# sac_4klep.net
KiCad netlist of a schematic drawn in EAGLE
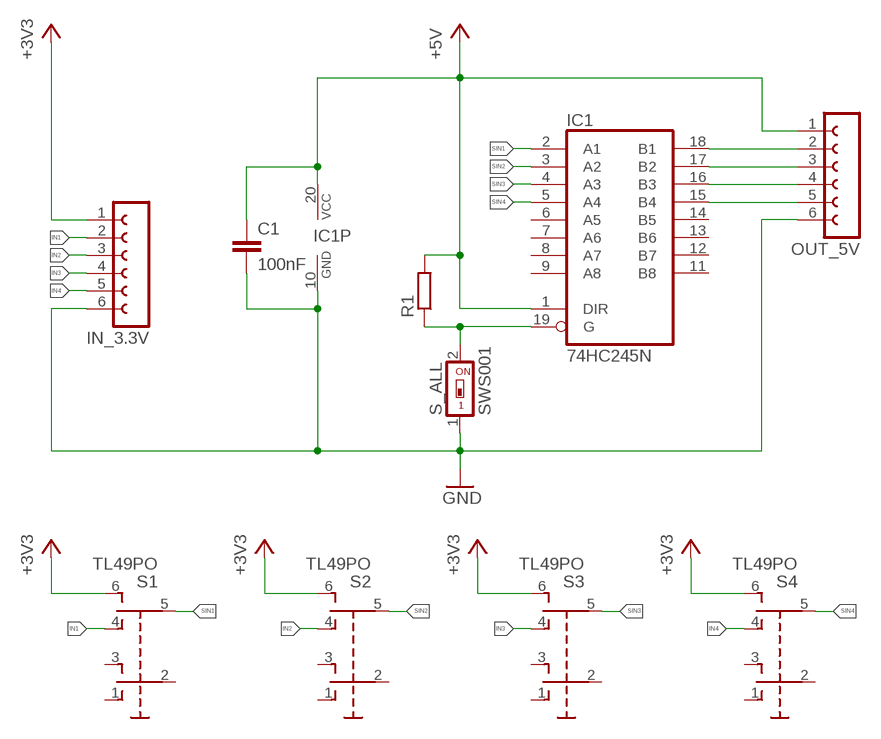
[diagram p0: schematic, sheet 1]

(export (version "E")
  (design (tool "Eeschema 10.0.6"))
  (components
    (comp (ref "C1")
      (value "100nF")
      (footprint "eagle-import:C025-040X050")
      (libsource (lib "eagle-import") (part "C-EU025-040X050"))
    )
    (comp (ref "IC1")
      (value "74HC245N")
      (footprint "eagle-import:DIL20")
      (libsource (lib "eagle-import") (part "74245NHC"))
    )
    (comp (ref "IN_3.3V")
      (value "FE06-1")
      (footprint "eagle-import:FE06")
      (libsource (lib "eagle-import") (part "FE06-1"))
    )
    (comp (ref "OUT_5V")
      (value "FE06-1")
      (footprint "eagle-import:FE06")
      (libsource (lib "eagle-import") (part "FE06-1"))
    )
    (comp (ref "R1")
      (value "R-EU_0204/5")
      (footprint "eagle-import:0204_5")
      (libsource (lib "eagle-import") (part "R-EU_0204/5"))
    )
    (comp (ref "S1")
      (value "TL49PO")
      (footprint "eagle-import:TL4XPO")
      (libsource (lib "eagle-import") (part "TL49PO"))
    )
    (comp (ref "S2")
      (value "TL49PO")
      (footprint "eagle-import:TL4XPO")
      (libsource (lib "eagle-import") (part "TL49PO"))
    )
    (comp (ref "S3")
      (value "TL49PO")
      (footprint "eagle-import:TL4XPO")
      (libsource (lib "eagle-import") (part "TL49PO"))
    )
    (comp (ref "S4")
      (value "TL49PO")
      (footprint "eagle-import:TL4XPO")
      (libsource (lib "eagle-import") (part "TL49PO"))
    )
    (comp (ref "S_ALL")
      (value "SWS001")
      (footprint "eagle-import:SMS-001")
      (libsource (lib "eagle-import") (part "SWS001"))
    )
  )
  (nets
    (net (code "1") (name "+3V3") (class "Default")
      (node (ref "IN_3.3V") (pin "1") (pinfunction "1_1") (pintype "passive"))
      (node (ref "S1") (pin "6") (pinfunction "S1_6") (pintype "passive"))
      (node (ref "S2") (pin "6") (pinfunction "S1_6") (pintype "passive"))
      (node (ref "S3") (pin "6") (pinfunction "S1_6") (pintype "passive"))
      (node (ref "S4") (pin "6") (pinfunction "S1_6") (pintype "passive"))
    )
    (net (code "2") (name "+5V") (class "Default")
      (node (ref "C1") (pin "1") (pinfunction "1_1") (pintype "passive"))
      (node (ref "IC1") (pin "1") (pinfunction "DIR_1") (pintype "input"))
      (node (ref "IC1") (pin "20") (pinfunction "VCC_20") (pintype "power_in"))
      (node (ref "OUT_5V") (pin "1") (pinfunction "1_1") (pintype "passive"))
      (node (ref "R1") (pin "2") (pinfunction "2_2") (pintype "passive"))
    )
    (net (code "3") (name "GND") (class "Default")
      (node (ref "C1") (pin "2") (pinfunction "2_2") (pintype "passive"))
      (node (ref "IC1") (pin "10") (pinfunction "GND_10") (pintype "power_in"))
      (node (ref "IN_3.3V") (pin "6") (pinfunction "6_6") (pintype "passive"))
      (node (ref "OUT_5V") (pin "6") (pinfunction "6_6") (pintype "passive"))
      (node (ref "S_ALL") (pin "1") (pinfunction "1_1") (pintype "passive"))
    )
    (net (code "4") (name "IN1") (class "Default")
      (node (ref "IN_3.3V") (pin "2") (pinfunction "2_2") (pintype "passive"))
      (node (ref "S1") (pin "4") (pinfunction "O1_4") (pintype "passive"))
    )
    (net (code "5") (name "IN2") (class "Default")
      (node (ref "IN_3.3V") (pin "3") (pinfunction "3_3") (pintype "passive"))
      (node (ref "S2") (pin "4") (pinfunction "O1_4") (pintype "passive"))
    )
    (net (code "6") (name "IN3") (class "Default")
      (node (ref "IN_3.3V") (pin "4") (pinfunction "4_4") (pintype "passive"))
      (node (ref "S3") (pin "4") (pinfunction "O1_4") (pintype "passive"))
    )
    (net (code "7") (name "IN4") (class "Default")
      (node (ref "IN_3.3V") (pin "5") (pinfunction "5_5") (pintype "passive"))
      (node (ref "S4") (pin "4") (pinfunction "O1_4") (pintype "passive"))
    )
    (net (code "8") (name "Net-(IC1A-B1)") (class "Default")
      (node (ref "IC1") (pin "18") (pinfunction "B1_18") (pintype "bidirectional"))
      (node (ref "OUT_5V") (pin "2") (pinfunction "2_2") (pintype "passive"))
    )
    (net (code "9") (name "Net-(IC1A-B2)") (class "Default")
      (node (ref "IC1") (pin "17") (pinfunction "B2_17") (pintype "bidirectional"))
      (node (ref "OUT_5V") (pin "3") (pinfunction "3_3") (pintype "passive"))
    )
    (net (code "10") (name "Net-(IC1A-B3)") (class "Default")
      (node (ref "IC1") (pin "16") (pinfunction "B3_16") (pintype "bidirectional"))
      (node (ref "OUT_5V") (pin "4") (pinfunction "4_4") (pintype "passive"))
    )
    (net (code "11") (name "Net-(IC1A-B4)") (class "Default")
      (node (ref "IC1") (pin "15") (pinfunction "B4_15") (pintype "bidirectional"))
      (node (ref "OUT_5V") (pin "5") (pinfunction "5_5") (pintype "passive"))
    )
    (net (code "12") (name "Net-(IC1A-G)") (class "Default")
      (node (ref "IC1") (pin "19") (pinfunction "G_19") (pintype "input"))
      (node (ref "R1") (pin "1") (pinfunction "1_1") (pintype "passive"))
      (node (ref "S_ALL") (pin "2") (pinfunction "2_2") (pintype "passive"))
    )
    (net (code "13") (name "SIN1") (class "Default")
      (node (ref "IC1") (pin "2") (pinfunction "A1_2") (pintype "bidirectional"))
      (node (ref "S1") (pin "5") (pinfunction "P1_5") (pintype "passive"))
    )
    (net (code "14") (name "SIN2") (class "Default")
      (node (ref "IC1") (pin "3") (pinfunction "A2_3") (pintype "bidirectional"))
      (node (ref "S2") (pin "5") (pinfunction "P1_5") (pintype "passive"))
    )
    (net (code "15") (name "SIN3") (class "Default")
      (node (ref "IC1") (pin "4") (pinfunction "A3_4") (pintype "bidirectional"))
      (node (ref "S3") (pin "5") (pinfunction "P1_5") (pintype "passive"))
    )
    (net (code "16") (name "SIN4") (class "Default")
      (node (ref "IC1") (pin "5") (pinfunction "A4_5") (pintype "bidirectional"))
      (node (ref "S4") (pin "5") (pinfunction "P1_5") (pintype "passive"))
    )
    (net (code "17") (name "unconnected-(IC1A-A5-Pad6)") (class "Default")
      (node (ref "IC1") (pin "6") (pinfunction "A5_6") (pintype "bidirectional"))
    )
    (net (code "18") (name "unconnected-(IC1A-A6-Pad7)") (class "Default")
      (node (ref "IC1") (pin "7") (pinfunction "A6_7") (pintype "bidirectional"))
    )
    (net (code "19") (name "unconnected-(IC1A-A7-Pad8)") (class "Default")
      (node (ref "IC1") (pin "8") (pinfunction "A7_8") (pintype "bidirectional"))
    )
    (net (code "20") (name "unconnected-(IC1A-A8-Pad9)") (class "Default")
      (node (ref "IC1") (pin "9") (pinfunction "A8_9") (pintype "bidirectional"))
    )
    (net (code "21") (name "unconnected-(IC1A-B5-Pad14)") (class "Default")
      (node (ref "IC1") (pin "14") (pinfunction "B5_14") (pintype "bidirectional"))
    )
    (net (code "22") (name "unconnected-(IC1A-B6-Pad13)") (class "Default")
      (node (ref "IC1") (pin "13") (pinfunction "B6_13") (pintype "bidirectional"))
    )
    (net (code "23") (name "unconnected-(IC1A-B7-Pad12)") (class "Default")
      (node (ref "IC1") (pin "12") (pinfunction "B7_12") (pintype "bidirectional"))
    )
    (net (code "24") (name "unconnected-(IC1A-B8-Pad11)") (class "Default")
      (node (ref "IC1") (pin "11") (pinfunction "B8_11") (pintype "bidirectional"))
    )
    (net (code "25") (name "unconnected-(S1-O-Pad1)") (class "Default")
      (node (ref "S1") (pin "1") (pinfunction "O_1") (pintype "passive"))
    )
    (net (code "26") (name "unconnected-(S1-P-Pad2)") (class "Default")
      (node (ref "S1") (pin "2") (pinfunction "P_2") (pintype "passive"))
    )
    (net (code "27") (name "unconnected-(S1-S-Pad3)") (class "Default")
      (node (ref "S1") (pin "3") (pinfunction "S_3") (pintype "passive"))
    )
    (net (code "28") (name "unconnected-(S2-O-Pad1)") (class "Default")
      (node (ref "S2") (pin "1") (pinfunction "O_1") (pintype "passive"))
    )
    (net (code "29") (name "unconnected-(S2-P-Pad2)") (class "Default")
      (node (ref "S2") (pin "2") (pinfunction "P_2") (pintype "passive"))
    )
    (net (code "30") (name "unconnected-(S2-S-Pad3)") (class "Default")
      (node (ref "S2") (pin "3") (pinfunction "S_3") (pintype "passive"))
    )
    (net (code "31") (name "unconnected-(S3-O-Pad1)") (class "Default")
      (node (ref "S3") (pin "1") (pinfunction "O_1") (pintype "passive"))
    )
    (net (code "32") (name "unconnected-(S3-P-Pad2)") (class "Default")
      (node (ref "S3") (pin "2") (pinfunction "P_2") (pintype "passive"))
    )
    (net (code "33") (name "unconnected-(S3-S-Pad3)") (class "Default")
      (node (ref "S3") (pin "3") (pinfunction "S_3") (pintype "passive"))
    )
    (net (code "34") (name "unconnected-(S4-O-Pad1)") (class "Default")
      (node (ref "S4") (pin "1") (pinfunction "O_1") (pintype "passive"))
    )
    (net (code "35") (name "unconnected-(S4-P-Pad2)") (class "Default")
      (node (ref "S4") (pin "2") (pinfunction "P_2") (pintype "passive"))
    )
    (net (code "36") (name "unconnected-(S4-S-Pad3)") (class "Default")
      (node (ref "S4") (pin "3") (pinfunction "S_3") (pintype "passive"))
    )
  )
)
